# FourInOneSensorBoardCO2-V1_0.net
KiCad netlist of a schematic drawn in Altium Designer
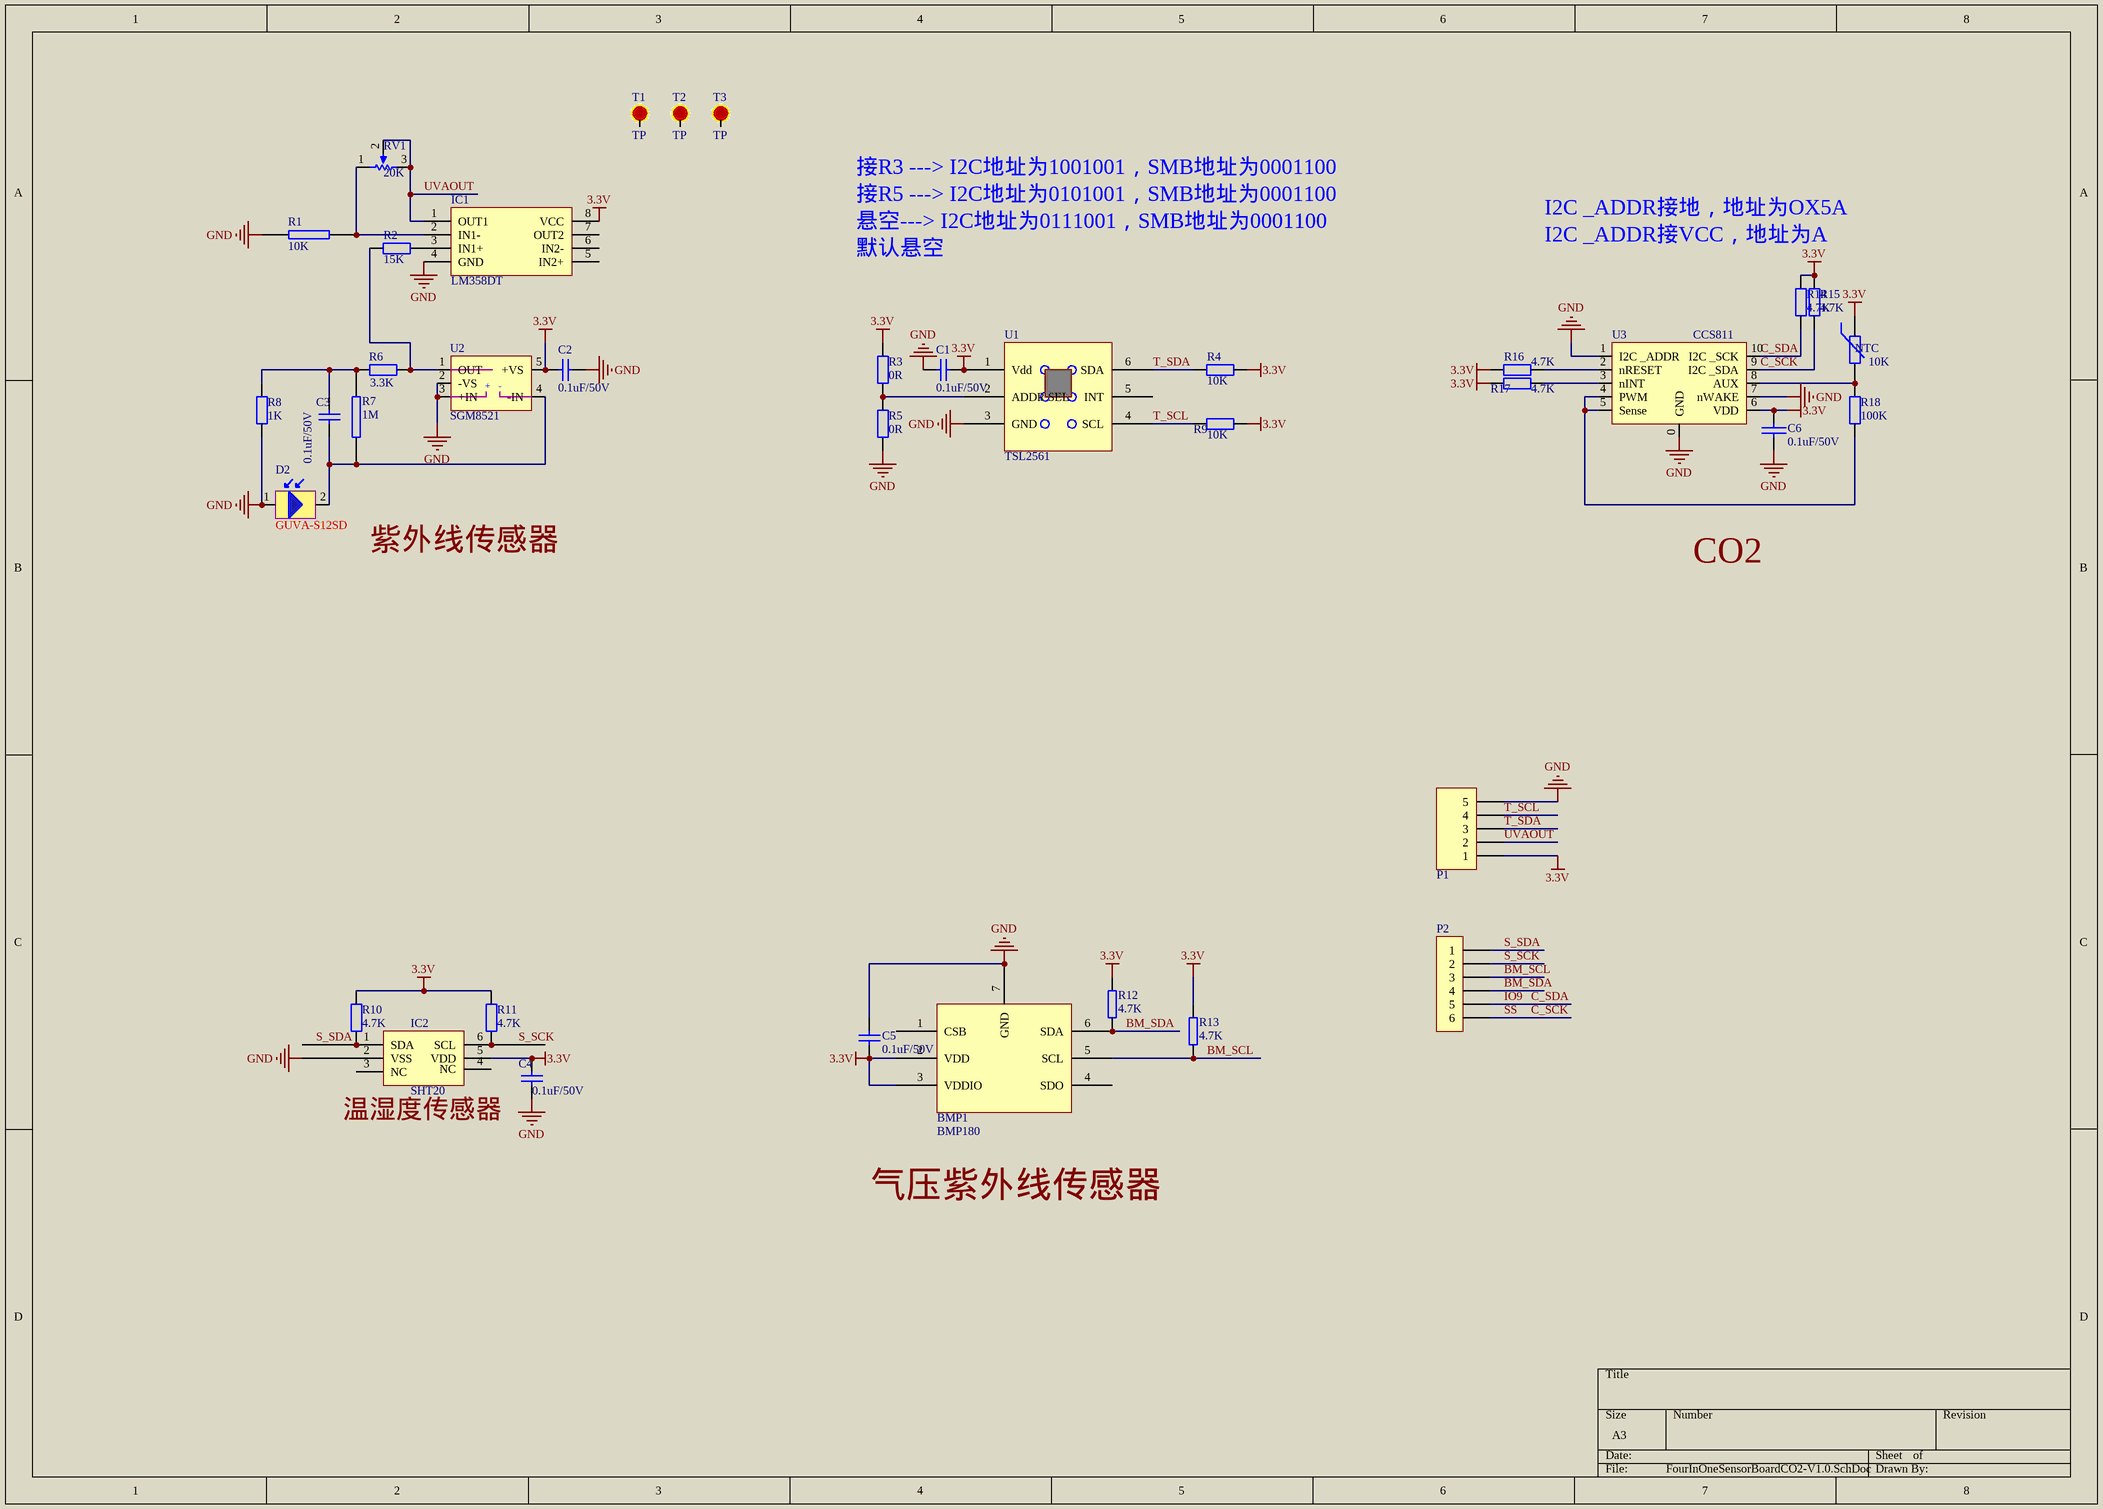
[diagram p0: FourInOneSensorBoardCO2-V1.0.SchDoc]

(export (version "E")
  (design (tool "Eeschema 10.0.6"))
  (components
    (comp (ref "BMP1")
      (value "BMP180")
      (footprint "BMP180")
      (description "气压传感器")
      (libsource (lib "AirPlaneSign") (part "BMP180"))
    )
    (comp (ref "C1")
      (value "0.1uF/50V")
      (footprint "C-0603")
      (description "贴片电容")
      (fields (field (name "PUBLISHER") "Altium Limited"))
      (libsource (lib "AirPlaneSign") (part "Cap"))
    )
    (comp (ref "C2")
      (value "0.1uF/50V")
      (footprint "C-0603")
      (description "贴片电容")
      (fields (field (name "PUBLISHER") "Altium Limited"))
      (libsource (lib "AirPlaneSign") (part "Cap"))
    )
    (comp (ref "C3")
      (value "0.1uF/50V")
      (footprint "C-0603")
      (description "贴片电容")
      (fields (field (name "PUBLISHER") "Altium Limited"))
      (libsource (lib "AirPlaneSign") (part "Cap"))
    )
    (comp (ref "C4")
      (value "0.1uF/50V")
      (footprint "C-0603")
      (description "贴片电容")
      (fields (field (name "PUBLISHER") "Altium Limited"))
      (libsource (lib "AirPlaneSign") (part "Cap"))
    )
    (comp (ref "C5")
      (value "0.1uF/50V")
      (footprint "C-0603")
      (description "贴片电容")
      (fields (field (name "PUBLISHER") "Altium Limited"))
      (libsource (lib "") (part "Cap_1"))
    )
    (comp (ref "C6")
      (value "0.1uF/50V")
      (footprint "C-0603")
      (description "贴片电容")
      (libsource (lib "*") (part "CAP"))
    )
    (comp (ref "D2")
      (value "GUVA-S12SD")
      (footprint "GUVA-S12SD")
      (description "紫外线传感器")
      (fields (field (name "PUBLISHER") "Altium Limited"))
      (libsource (lib "AirPlaneSign") (part "GUVA-S12SD"))
    )
    (comp (ref "IC1")
      (value "LM358DT")
      (footprint "SOIC8_39MM")
      (description "通用运放")
      (libsource (lib "AirPlaneSign") (part "LM358DT"))
    )
    (comp (ref "IC2")
      (value "SHT20")
      (footprint "SHT20")
      (description "温湿度传感器")
      (libsource (lib "AirPlaneSign") (part "SHT20"))
    )
    (comp (ref "NTC")
      (value "10K")
      (footprint "NTC")
      (description "热敏电阻")
      (fields (field (name "PUBLISHER") "Altium Limited"))
      (libsource (lib "SCHEMATIC") (part "RES-NTC/PTC"))
    )
    (comp (ref "P1")
      (value "JXT-5-l")
      (footprint "JXT-5-l")
      (description "1.27立式贴片针座")
      (fields (field (name "PUBLISHER") "Altium Limited"))
      (libsource (lib "AirPlaneSign") (part "Header 5"))
    )
    (comp (ref "P2")
      (value "JXT-6-I")
      (footprint "JXT-6-l")
      (description "1.27立式贴片针座")
      (fields (field (name "PUBLISHER") "Altium Limited"))
      (libsource (lib "AirPlaneSign") (part "Header 6"))
    )
    (comp (ref "R1")
      (value "10K")
      (footprint "R-0603")
      (description "贴片电阻")
      (libsource (lib "Miscellaneous Devices") (part "RES2"))
    )
    (comp (ref "R2")
      (value "15K")
      (footprint "R-0603")
      (description "贴片电阻")
      (fields (field (name "PUBLISHER") "Altium Limited"))
      (libsource (lib "") (part "Res2_2"))
    )
    (comp (ref "R3")
      (value "0R")
      (footprint "R-0603")
      (description "贴片电阻")
      (fields (field (name "PUBLISHER") "Altium Limited"))
      (libsource (lib "") (part "Res2_3"))
    )
    (comp (ref "R4")
      (value "10K")
      (footprint "R-0603")
      (description "贴片电阻")
      (fields (field (name "PUBLISHER") "Altium Limited"))
      (libsource (lib "") (part "Res2_2"))
    )
    (comp (ref "R5")
      (value "0R")
      (footprint "R-0603")
      (description "贴片电阻")
      (fields (field (name "PUBLISHER") "Altium Limited"))
      (libsource (lib "") (part "Res2_1"))
    )
    (comp (ref "R6")
      (value "3.3K")
      (footprint "R-0603")
      (description "贴片电阻")
      (fields (field (name "PUBLISHER") "Altium Limited"))
      (libsource (lib "") (part "Res2_2"))
    )
    (comp (ref "R7")
      (value "1M")
      (footprint "R-0603")
      (description "贴片电阻")
      (libsource (lib "Cha") (part "RES2"))
    )
    (comp (ref "R8")
      (value "1K")
      (footprint "R-0603")
      (description "贴片电阻")
      (fields (field (name "PUBLISHER") "Altium Limited"))
      (libsource (lib "") (part "Res2_1"))
    )
    (comp (ref "R9")
      (value "10K")
      (footprint "R-0603")
      (description "贴片电阻")
      (fields (field (name "PUBLISHER") "Altium Limited"))
      (libsource (lib "Miscellaneous Devices") (part "Res2"))
    )
    (comp (ref "R10")
      (value "4.7K")
      (footprint "R-0603")
      (description "贴片电阻")
      (fields (field (name "PUBLISHER") "Altium Limited"))
      (libsource (lib "") (part "Res2_1"))
    )
    (comp (ref "R11")
      (value "4.7K")
      (footprint "R-0603")
      (description "贴片电阻")
      (fields (field (name "PUBLISHER") "Altium Limited"))
      (libsource (lib "") (part "Res2_1"))
    )
    (comp (ref "R12")
      (value "4.7K")
      (footprint "R-0603")
      (description "贴片电阻")
      (libsource (lib "FM") (part "RES2"))
    )
    (comp (ref "R13")
      (value "4.7K")
      (footprint "R-0603")
      (description "贴片电阻")
      (libsource (lib "FM") (part "RES2"))
    )
    (comp (ref "R14")
      (value "4.7K")
      (footprint "R-0603")
      (description "贴片电阻")
      (fields (field (name "PUBLISHER") "Altium Limited"))
      (libsource (lib "") (part "Res2_3"))
    )
    (comp (ref "R15")
      (value "4.7K")
      (footprint "R-0603")
      (description "贴片电阻")
      (fields (field (name "PUBLISHER") "Altium Limited"))
      (libsource (lib "") (part "Res2_3"))
    )
    (comp (ref "R16")
      (value "4.7K")
      (footprint "R-0603")
      (description "贴片电阻")
      (fields (field (name "PUBLISHER") "Altium Limited"))
      (libsource (lib "") (part "Res2_2"))
    )
    (comp (ref "R17")
      (value "4.7K")
      (footprint "R-0603")
      (description "贴片电阻")
      (fields (field (name "PUBLISHER") "Altium Limited"))
      (libsource (lib "") (part "Res2_2"))
    )
    (comp (ref "R18")
      (value "100K")
      (footprint "R-0603")
      (description "贴片电阻")
      (fields (field (name "PUBLISHER") "Altium Limited"))
      (libsource (lib "") (part "Res2_3"))
    )
    (comp (ref "RV1")
      (value "20K")
      (footprint "VR3362P")
      (description "滑动变阻")
      (libsource (lib "AirPlaneSign") (part "RV_1"))
    )
    (comp (ref "T1") (value "TP") (footprint "安装孔-M6") (libsource (lib "AirPlaneSign") (part "TP")))
    (comp (ref "T2") (value "TP") (footprint "安装孔-M6") (libsource (lib "AirPlaneSign") (part "TP")))
    (comp (ref "T3") (value "TP") (footprint "安装孔-M6") (libsource (lib "AirPlaneSign") (part "TP")))
    (comp (ref "U1")
      (value "TSL2561")
      (footprint "TSL2561_FN")
      (description "光照度传感器")
      (libsource (lib "AirPlaneSign") (part "TSL2561"))
    )
    (comp (ref "U2")
      (value "SGM8521")
      (footprint "SOT-23-5")
      (description "低功耗运放")
      (libsource (lib "AirPlaneSign") (part "SGM8521"))
    )
    (comp (ref "U3")
      (value "CCS811")
      (footprint "CCS811")
      (description "CO2传感器")
      (libsource (lib "AirPlaneSign") (part "CCS811"))
    )
  )
  (nets
    (net (code "1") (name "/BM_SCL") (class "Default")
      (node (ref "BMP1") (pin "5") (pinfunction "SCL_5") (pintype "passive"))
      (node (ref "P2") (pin "3") (pinfunction "3_3") (pintype "passive"))
      (node (ref "R13") (pin "1") (pinfunction "1_1") (pintype "passive"))
    )
    (net (code "2") (name "/BM_SDA") (class "Default")
      (node (ref "BMP1") (pin "6") (pinfunction "SDA_6") (pintype "passive"))
      (node (ref "P2") (pin "4") (pinfunction "4_4") (pintype "passive"))
      (node (ref "R12") (pin "1") (pinfunction "1_1") (pintype "passive"))
    )
    (net (code "3") (name "/C_SCK") (class "Default")
      (node (ref "P2") (pin "6") (pinfunction "6_6") (pintype "passive"))
      (node (ref "R15") (pin "2") (pinfunction "2_2") (pintype "passive"))
      (node (ref "U3") (pin "9") (pinfunction "I2C__SDA_9") (pintype "passive"))
    )
    (net (code "4") (name "/C_SDA") (class "Default")
      (node (ref "P2") (pin "5") (pinfunction "5_5") (pintype "passive"))
      (node (ref "R14") (pin "2") (pinfunction "2_2") (pintype "passive"))
      (node (ref "U3") (pin "10") (pinfunction "I2C__SCK_10") (pintype "passive"))
    )
    (net (code "5") (name "/S_SCK") (class "Default")
      (node (ref "IC2") (pin "6") (pinfunction "SCL_6") (pintype "passive"))
      (node (ref "P2") (pin "2") (pinfunction "2_2") (pintype "passive"))
      (node (ref "R11") (pin "1") (pinfunction "1_1") (pintype "passive"))
    )
    (net (code "6") (name "/S_SDA") (class "Default")
      (node (ref "IC2") (pin "1") (pinfunction "SDA_1") (pintype "passive"))
      (node (ref "P2") (pin "1") (pinfunction "1_1") (pintype "passive"))
      (node (ref "R10") (pin "1") (pinfunction "1_1") (pintype "passive"))
    )
    (net (code "7") (name "/T_SCL") (class "Default")
      (node (ref "P1") (pin "4") (pinfunction "4_4") (pintype "passive"))
      (node (ref "R9") (pin "1") (pinfunction "1_1") (pintype "passive"))
      (node (ref "U1") (pin "4") (pinfunction "SCL_4") (pintype "passive"))
    )
    (net (code "8") (name "/T_SDA") (class "Default")
      (node (ref "P1") (pin "3") (pinfunction "3_3") (pintype "passive"))
      (node (ref "R4") (pin "2") (pinfunction "2_2") (pintype "passive"))
      (node (ref "U1") (pin "6") (pinfunction "SDA_6") (pintype "passive"))
    )
    (net (code "9") (name "/UVAOUT") (class "Default")
      (node (ref "IC1") (pin "1") (pinfunction "OUT1_1") (pintype "passive"))
      (node (ref "P1") (pin "2") (pinfunction "2_2") (pintype "passive"))
      (node (ref "RV1") (pin "2") (pinfunction "TAP_2") (pintype "passive"))
      (node (ref "RV1") (pin "3") (pinfunction "TOP_3") (pintype "passive"))
    )
    (net (code "10") (name "3.3V") (class "Default")
      (node (ref "BMP1") (pin "2") (pinfunction "VDD_2") (pintype "passive"))
      (node (ref "BMP1") (pin "3") (pinfunction "VDDIO_3") (pintype "passive"))
      (node (ref "C1") (pin "1") (pinfunction "1_1") (pintype "passive"))
      (node (ref "C2") (pin "2") (pinfunction "2_2") (pintype "passive"))
      (node (ref "C4") (pin "1") (pinfunction "1_1") (pintype "passive"))
      (node (ref "C5") (pin "2") (pinfunction "2_2") (pintype "passive"))
      (node (ref "C6") (pin "1") (pinfunction "1_1") (pintype "passive"))
      (node (ref "IC1") (pin "8") (pinfunction "VCC_8") (pintype "passive"))
      (node (ref "IC2") (pin "5") (pinfunction "VDD_5") (pintype "passive"))
      (node (ref "NTC") (pin "1") (pinfunction "1_1") (pintype "passive"))
      (node (ref "P1") (pin "1") (pinfunction "1_1") (pintype "passive"))
      (node (ref "R10") (pin "2") (pinfunction "2_2") (pintype "passive"))
      (node (ref "R11") (pin "2") (pinfunction "2_2") (pintype "passive"))
      (node (ref "R12") (pin "2") (pinfunction "2_2") (pintype "passive"))
      (node (ref "R13") (pin "2") (pinfunction "2_2") (pintype "passive"))
      (node (ref "R14") (pin "1") (pinfunction "1_1") (pintype "passive"))
      (node (ref "R15") (pin "1") (pinfunction "1_1") (pintype "passive"))
      (node (ref "R16") (pin "2") (pinfunction "2_2") (pintype "passive"))
      (node (ref "R17") (pin "2") (pinfunction "2_2") (pintype "passive"))
      (node (ref "R3") (pin "1") (pinfunction "1_1") (pintype "passive"))
      (node (ref "R4") (pin "1") (pinfunction "1_1") (pintype "passive"))
      (node (ref "R9") (pin "2") (pinfunction "2_2") (pintype "passive"))
      (node (ref "U1") (pin "1") (pinfunction "Vdd_1") (pintype "passive"))
      (node (ref "U2") (pin "5") (pinfunction "+VS_5") (pintype "passive"))
      (node (ref "U3") (pin "6") (pinfunction "VDD_6") (pintype "passive"))
    )
    (net (code "11") (name "GND") (class "Default")
      (node (ref "BMP1") (pin "7") (pinfunction "GND_7") (pintype "passive"))
      (node (ref "C1") (pin "2") (pinfunction "2_2") (pintype "passive"))
      (node (ref "C2") (pin "1") (pinfunction "1_1") (pintype "passive"))
      (node (ref "C4") (pin "2") (pinfunction "2_2") (pintype "passive"))
      (node (ref "C5") (pin "1") (pinfunction "1_1") (pintype "passive"))
      (node (ref "C6") (pin "2") (pinfunction "2_2") (pintype "passive"))
      (node (ref "D2") (pin "1") (pinfunction "1_1") (pintype "passive"))
      (node (ref "IC1") (pin "4") (pinfunction "GND_4") (pintype "passive"))
      (node (ref "IC2") (pin "2") (pinfunction "VSS_2") (pintype "passive"))
      (node (ref "P1") (pin "5") (pinfunction "5_5") (pintype "passive"))
      (node (ref "R1") (pin "1") (pinfunction "1_1") (pintype "passive"))
      (node (ref "R5") (pin "1") (pinfunction "1_1") (pintype "passive"))
      (node (ref "R8") (pin "1") (pinfunction "1_1") (pintype "passive"))
      (node (ref "U1") (pin "3") (pinfunction "GND_3") (pintype "passive"))
      (node (ref "U2") (pin "2") (pinfunction "-VS_2") (pintype "passive"))
      (node (ref "U2") (pin "3") (pinfunction "+IN_3") (pintype "passive"))
      (node (ref "U3") (pin "0") (pinfunction "GND_0") (pintype "passive"))
      (node (ref "U3") (pin "1") (pinfunction "I2C__ADDR_1") (pintype "passive"))
      (node (ref "U3") (pin "7") (pinfunction "nWAKE_7") (pintype "passive"))
    )
    (net (code "12") (name "Net-(C3-Pad1)") (class "Default")
      (node (ref "C3") (pin "1") (pinfunction "1_1") (pintype "passive"))
      (node (ref "R6") (pin "2") (pinfunction "2_2") (pintype "passive"))
      (node (ref "R7") (pin "1") (pinfunction "1_1") (pintype "passive"))
      (node (ref "R8") (pin "2") (pinfunction "2_2") (pintype "passive"))
    )
    (net (code "13") (name "Net-(IC1-IN1+)") (class "Default")
      (node (ref "IC1") (pin "3") (pinfunction "IN1+_3") (pintype "passive"))
      (node (ref "R2") (pin "1") (pinfunction "1_1") (pintype "passive"))
    )
    (net (code "14") (name "Net-(IC1-IN1-)") (class "Default")
      (node (ref "IC1") (pin "2") (pinfunction "IN1-_2") (pintype "passive"))
      (node (ref "R1") (pin "2") (pinfunction "2_2") (pintype "passive"))
      (node (ref "RV1") (pin "1") (pinfunction "BOT_1") (pintype "passive"))
    )
    (net (code "15") (name "Net-(U1-ADDR_SEL)") (class "Default")
      (node (ref "R3") (pin "2") (pinfunction "2_2") (pintype "passive"))
      (node (ref "R5") (pin "2") (pinfunction "2_2") (pintype "passive"))
      (node (ref "U1") (pin "2") (pinfunction "ADDR_SEL_2") (pintype "passive"))
    )
    (net (code "16") (name "Net-(U2--IN)") (class "Default")
      (node (ref "C3") (pin "2") (pinfunction "2_2") (pintype "passive"))
      (node (ref "D2") (pin "2") (pinfunction "2_2") (pintype "passive"))
      (node (ref "R7") (pin "2") (pinfunction "2_2") (pintype "passive"))
      (node (ref "U2") (pin "4") (pinfunction "-IN_4") (pintype "passive"))
    )
    (net (code "17") (name "Net-(U2-OUT)") (class "Default")
      (node (ref "R2") (pin "2") (pinfunction "2_2") (pintype "passive"))
      (node (ref "R6") (pin "1") (pinfunction "1_1") (pintype "passive"))
      (node (ref "U2") (pin "1") (pinfunction "OUT_1") (pintype "passive"))
    )
    (net (code "18") (name "Net-(U3-AUX)") (class "Default")
      (node (ref "NTC") (pin "2") (pinfunction "2_2") (pintype "passive"))
      (node (ref "R18") (pin "1") (pinfunction "1_1") (pintype "passive"))
      (node (ref "U3") (pin "8") (pinfunction "AUX_8") (pintype "passive"))
    )
    (net (code "19") (name "Net-(U3-PWM)") (class "Default")
      (node (ref "R18") (pin "2") (pinfunction "2_2") (pintype "passive"))
      (node (ref "U3") (pin "4") (pinfunction "PWM_4") (pintype "passive"))
      (node (ref "U3") (pin "5") (pinfunction "Sense_5") (pintype "passive"))
    )
    (net (code "20") (name "Net-(U3-nINT)") (class "Default")
      (node (ref "R17") (pin "1") (pinfunction "1_1") (pintype "passive"))
      (node (ref "U3") (pin "3") (pinfunction "nINT_3") (pintype "passive"))
    )
    (net (code "21") (name "Net-(U3-nRESET)") (class "Default")
      (node (ref "R16") (pin "1") (pinfunction "1_1") (pintype "passive"))
      (node (ref "U3") (pin "2") (pinfunction "nRESET_2") (pintype "passive"))
    )
    (net (code "22") (name "unconnected-(BMP1-CSB-Pad1)") (class "Default")
      (node (ref "BMP1") (pin "1") (pinfunction "CSB_1") (pintype "passive"))
    )
    (net (code "23") (name "unconnected-(BMP1-SDO-Pad4)") (class "Default")
      (node (ref "BMP1") (pin "4") (pinfunction "SDO_4") (pintype "passive"))
    )
    (net (code "24") (name "unconnected-(IC1-IN2+-Pad5)") (class "Default")
      (node (ref "IC1") (pin "5") (pinfunction "IN2+_5") (pintype "passive"))
    )
    (net (code "25") (name "unconnected-(IC1-IN2--Pad6)") (class "Default")
      (node (ref "IC1") (pin "6") (pinfunction "IN2-_6") (pintype "passive"))
    )
    (net (code "26") (name "unconnected-(IC1-OUT2-Pad7)") (class "Default")
      (node (ref "IC1") (pin "7") (pinfunction "OUT2_7") (pintype "passive"))
    )
    (net (code "27") (name "unconnected-(IC2-NC-Pad3)") (class "Default")
      (node (ref "IC2") (pin "3") (pinfunction "NC_3") (pintype "passive"))
    )
    (net (code "28") (name "unconnected-(IC2-NC-Pad4)") (class "Default")
      (node (ref "IC2") (pin "4") (pinfunction "NC_4") (pintype "passive"))
    )
    (net (code "29") (name "unconnected-(T1-T-Pad1)") (class "Default")
      (node (ref "T1") (pin "1") (pinfunction "T_1") (pintype "passive"))
    )
    (net (code "30") (name "unconnected-(T2-T-Pad1)") (class "Default")
      (node (ref "T2") (pin "1") (pinfunction "T_1") (pintype "passive"))
    )
    (net (code "31") (name "unconnected-(T3-T-Pad1)") (class "Default")
      (node (ref "T3") (pin "1") (pinfunction "T_1") (pintype "passive"))
    )
    (net (code "32") (name "unconnected-(U1-INT-Pad5)") (class "Default")
      (node (ref "U1") (pin "5") (pinfunction "INT_5") (pintype "passive"))
    )
  )
)
